# seismometer_lcdboard.net
KiCad netlist of a schematic drawn in EAGLE
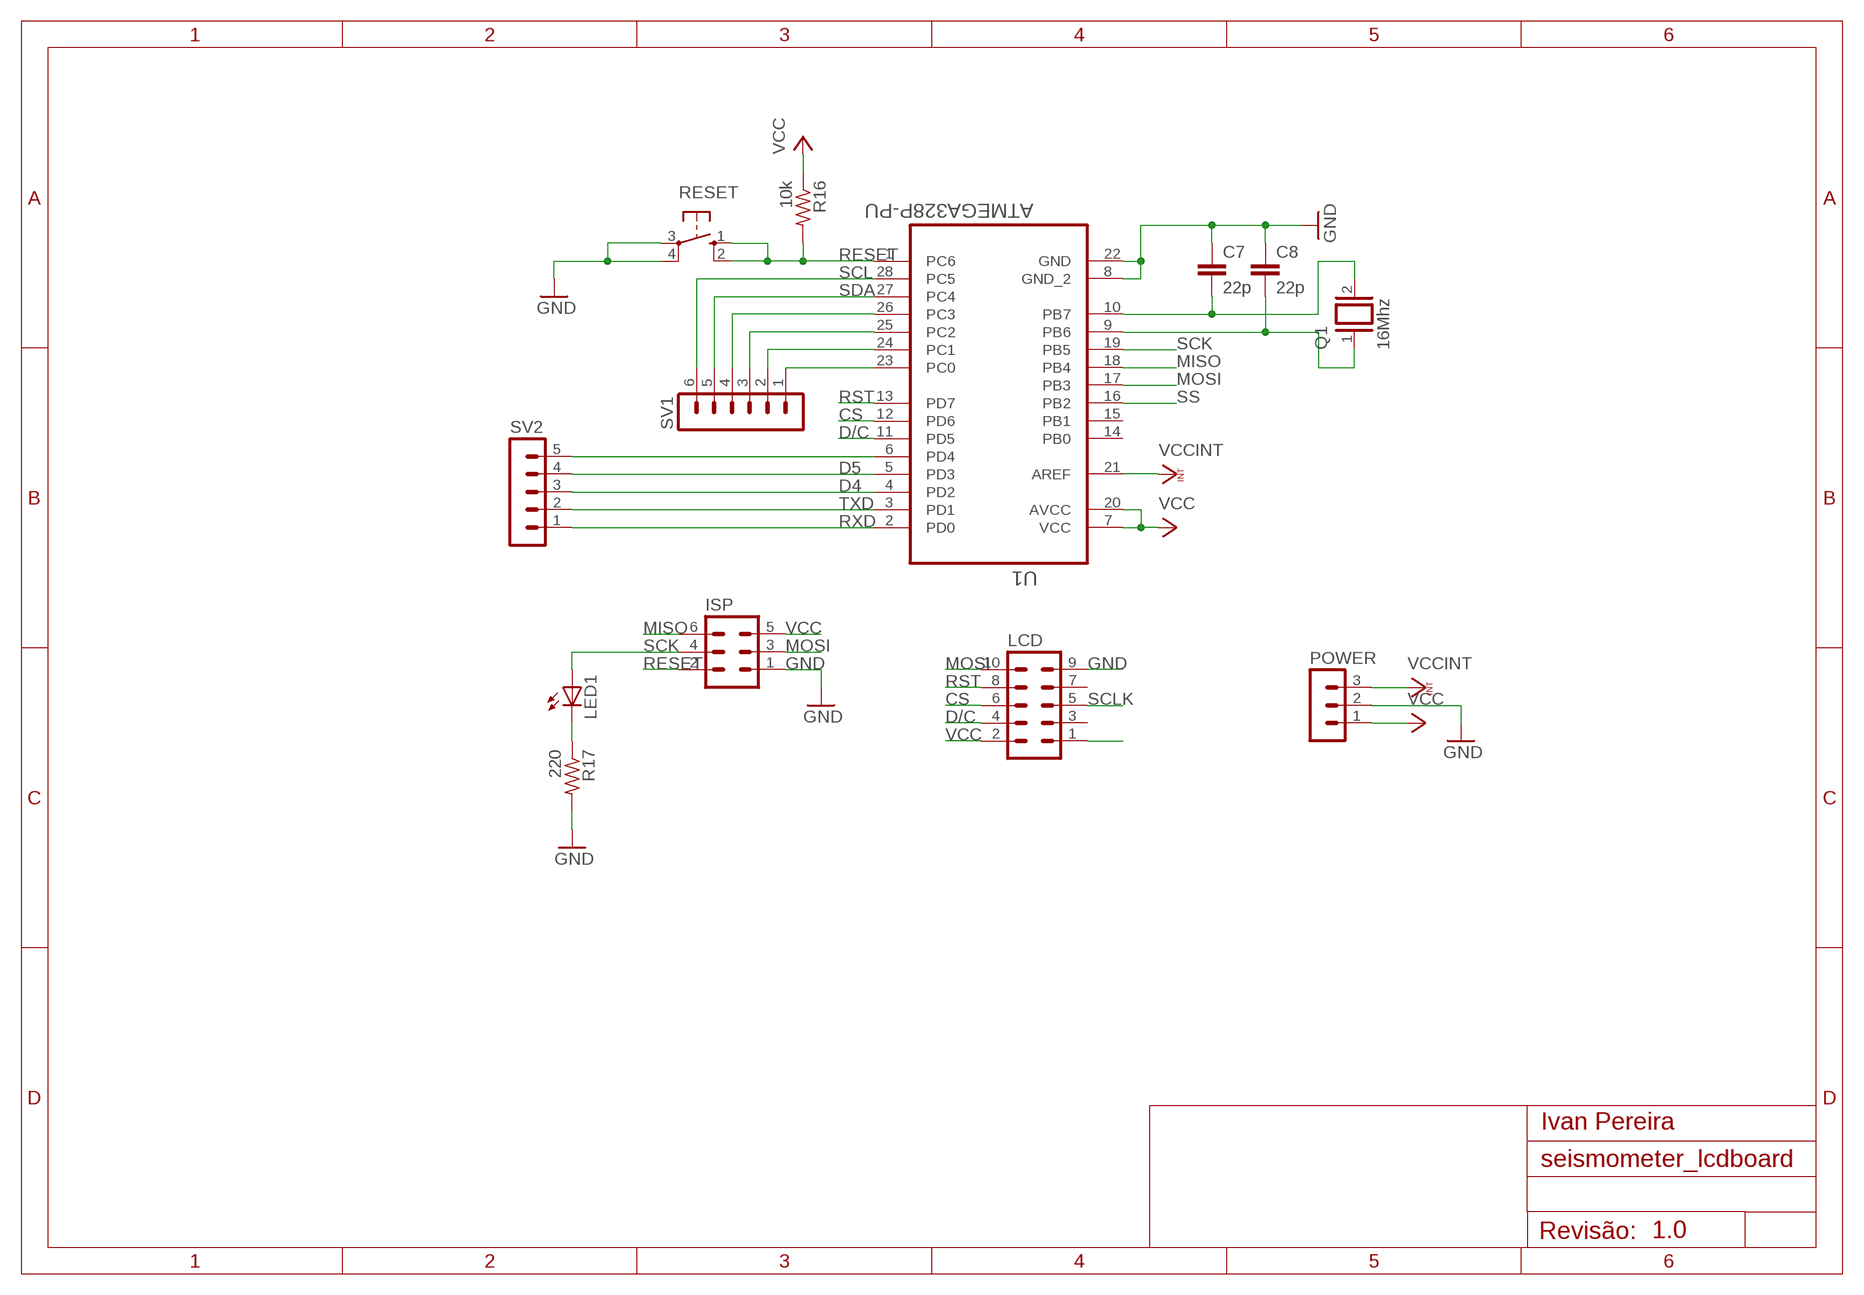
[diagram p0: schematic, sheet 1]

(export (version "E")
  (design (tool "Eeschema 10.0.6"))
  (components
    (comp (ref "C7")
      (value "22p")
      (footprint "eagle-import:C050-025X075")
      (libsource (lib "eagle-import") (part "C-EU050-025X075"))
    )
    (comp (ref "C8")
      (value "22p")
      (footprint "eagle-import:C050-025X075")
      (libsource (lib "eagle-import") (part "C-EU050-025X075"))
    )
    (comp (ref "ISP")
      (value "MA03-2")
      (footprint "eagle-import:MA03-2")
      (libsource (lib "eagle-import") (part "MA03-2"))
    )
    (comp (ref "LCD")
      (value "MA05-2")
      (footprint "eagle-import:MA05-2")
      (libsource (lib "eagle-import") (part "MA05-2"))
    )
    (comp (ref "LED1")
      (value "LED3MM")
      (footprint "eagle-import:LED3MM")
      (libsource (lib "eagle-import") (part "LED3MM"))
    )
    (comp (ref "POWER")
      (value "MA03-1")
      (footprint "eagle-import:MA03-1")
      (libsource (lib "eagle-import") (part "MA03-1"))
    )
    (comp (ref "Q1")
      (value "16Mhz")
      (footprint "eagle-import:QS")
      (libsource (lib "eagle-import") (part "XTAL/S"))
    )
    (comp (ref "R16")
      (value "10k")
      (footprint "eagle-import:0207_12")
      (libsource (lib "eagle-import") (part "R-US_0207/12"))
    )
    (comp (ref "R17")
      (value "220")
      (footprint "eagle-import:0207_12")
      (libsource (lib "eagle-import") (part "R-US_0207/12"))
    )
    (comp (ref "RESET")
      (value "10-XX")
      (footprint "eagle-import:B3F-10XX")
      (fields (field (name "MPN") "B3F-1000"))
      (libsource (lib "eagle-import") (part "10-XX"))
    )
    (comp (ref "SV1")
      (value "MA06-1")
      (footprint "eagle-import:MA06-1")
      (libsource (lib "eagle-import") (part "MA06-1"))
    )
    (comp (ref "SV2")
      (value "MA05-1")
      (footprint "eagle-import:MA05-1")
      (libsource (lib "eagle-import") (part "MA05-1"))
    )
    (comp (ref "U1")
      (value "ATMEGA328P-PU")
      (footprint "eagle-import:DIP254P762X457-28")
      (libsource (lib "eagle-import") (part "ATMEGA328P-PU"))
    )
  )
  (nets
    (net (code "1") (name "/CS") (class "Default")
      (node (ref "LCD") (pin "6") (pinfunction "6_6") (pintype "passive"))
      (node (ref "U1") (pin "12") (pinfunction "PD6_12") (pintype "bidirectional"))
    )
    (net (code "2") (name "/D4") (class "Default")
      (node (ref "SV2") (pin "3") (pinfunction "3_3") (pintype "passive"))
      (node (ref "U1") (pin "4") (pinfunction "PD2_4") (pintype "bidirectional"))
    )
    (net (code "3") (name "/D5") (class "Default")
      (node (ref "SV2") (pin "4") (pinfunction "4_4") (pintype "passive"))
      (node (ref "U1") (pin "5") (pinfunction "PD3_5") (pintype "bidirectional"))
    )
    (net (code "4") (name "/D{slash}C") (class "Default")
      (node (ref "LCD") (pin "4") (pinfunction "4_4") (pintype "passive"))
      (node (ref "U1") (pin "11") (pinfunction "PD5_11") (pintype "bidirectional"))
    )
    (net (code "5") (name "/MISO") (class "Default")
      (node (ref "ISP") (pin "6") (pinfunction "6_6") (pintype "passive"))
      (node (ref "U1") (pin "18") (pinfunction "PB4_18") (pintype "bidirectional"))
    )
    (net (code "6") (name "/MOSI") (class "Default")
      (node (ref "ISP") (pin "3") (pinfunction "3_3") (pintype "passive"))
      (node (ref "LCD") (pin "10") (pinfunction "10_10") (pintype "passive"))
      (node (ref "U1") (pin "17") (pinfunction "PB3_17") (pintype "bidirectional"))
    )
    (net (code "7") (name "/RESET") (class "Default")
      (node (ref "ISP") (pin "2") (pinfunction "2_2") (pintype "passive"))
      (node (ref "R16") (pin "2") (pinfunction "2_2") (pintype "passive"))
      (node (ref "RESET") (pin "1") (pinfunction "S_1") (pintype "passive"))
      (node (ref "RESET") (pin "2") (pinfunction "S1_2") (pintype "passive"))
      (node (ref "U1") (pin "1") (pinfunction "PC6_1") (pintype "bidirectional"))
    )
    (net (code "8") (name "/RST") (class "Default")
      (node (ref "LCD") (pin "8") (pinfunction "8_8") (pintype "passive"))
      (node (ref "U1") (pin "13") (pinfunction "PD7_13") (pintype "bidirectional"))
    )
    (net (code "9") (name "/RXD") (class "Default")
      (node (ref "SV2") (pin "1") (pinfunction "1_1") (pintype "passive"))
      (node (ref "U1") (pin "2") (pinfunction "PD0_2") (pintype "bidirectional"))
    )
    (net (code "10") (name "/SCK") (class "Default")
      (node (ref "ISP") (pin "4") (pinfunction "4_4") (pintype "passive"))
      (node (ref "LED1") (pin "A") (pinfunction "A_A") (pintype "passive"))
      (node (ref "U1") (pin "19") (pinfunction "PB5_19") (pintype "bidirectional"))
    )
    (net (code "11") (name "/SCL") (class "Default")
      (node (ref "SV1") (pin "6") (pinfunction "6_6") (pintype "passive"))
      (node (ref "U1") (pin "28") (pinfunction "PC5_28") (pintype "bidirectional"))
    )
    (net (code "12") (name "/SCLK") (class "Default")
      (node (ref "LCD") (pin "5") (pinfunction "5_5") (pintype "passive"))
    )
    (net (code "13") (name "/SDA") (class "Default")
      (node (ref "SV1") (pin "5") (pinfunction "5_5") (pintype "passive"))
      (node (ref "U1") (pin "27") (pinfunction "PC4_27") (pintype "bidirectional"))
    )
    (net (code "14") (name "/SS") (class "Default")
      (node (ref "U1") (pin "16") (pinfunction "PB2_16") (pintype "bidirectional"))
    )
    (net (code "15") (name "/TXD") (class "Default")
      (node (ref "SV2") (pin "2") (pinfunction "2_2") (pintype "passive"))
      (node (ref "U1") (pin "3") (pinfunction "PD1_3") (pintype "bidirectional"))
    )
    (net (code "16") (name "GND") (class "Default")
      (node (ref "C7") (pin "1") (pinfunction "1_1") (pintype "passive"))
      (node (ref "C8") (pin "1") (pinfunction "1_1") (pintype "passive"))
      (node (ref "ISP") (pin "1") (pinfunction "1_1") (pintype "passive"))
      (node (ref "LCD") (pin "9") (pinfunction "9_9") (pintype "passive"))
      (node (ref "POWER") (pin "2") (pinfunction "2_2") (pintype "passive"))
      (node (ref "R17") (pin "2") (pinfunction "2_2") (pintype "passive"))
      (node (ref "RESET") (pin "3") (pinfunction "P_3") (pintype "passive"))
      (node (ref "RESET") (pin "4") (pinfunction "P1_4") (pintype "passive"))
      (node (ref "U1") (pin "22") (pinfunction "GND_22") (pintype "passive"))
      (node (ref "U1") (pin "8") (pinfunction "GND_2_8") (pintype "passive"))
    )
    (net (code "17") (name "Net-(LED1-C)") (class "Default")
      (node (ref "LED1") (pin "K") (pinfunction "C_K") (pintype "passive"))
      (node (ref "R17") (pin "1") (pinfunction "1_1") (pintype "passive"))
    )
    (net (code "18") (name "Net-(U1-PB6)") (class "Default")
      (node (ref "C8") (pin "2") (pinfunction "2_2") (pintype "passive"))
      (node (ref "Q1") (pin "1") (pinfunction "1_1") (pintype "passive"))
      (node (ref "U1") (pin "9") (pinfunction "PB6_9") (pintype "bidirectional"))
    )
    (net (code "19") (name "Net-(U1-PB7)") (class "Default")
      (node (ref "C7") (pin "2") (pinfunction "2_2") (pintype "passive"))
      (node (ref "Q1") (pin "2") (pinfunction "2_2") (pintype "passive"))
      (node (ref "U1") (pin "10") (pinfunction "PB7_10") (pintype "bidirectional"))
    )
    (net (code "20") (name "Net-(U1-PC0)") (class "Default")
      (node (ref "SV1") (pin "1") (pinfunction "1_1") (pintype "passive"))
      (node (ref "U1") (pin "23") (pinfunction "PC0_23") (pintype "bidirectional"))
    )
    (net (code "21") (name "Net-(U1-PC1)") (class "Default")
      (node (ref "SV1") (pin "2") (pinfunction "2_2") (pintype "passive"))
      (node (ref "U1") (pin "24") (pinfunction "PC1_24") (pintype "bidirectional"))
    )
    (net (code "22") (name "Net-(U1-PC2)") (class "Default")
      (node (ref "SV1") (pin "3") (pinfunction "3_3") (pintype "passive"))
      (node (ref "U1") (pin "25") (pinfunction "PC2_25") (pintype "bidirectional"))
    )
    (net (code "23") (name "Net-(U1-PC3)") (class "Default")
      (node (ref "SV1") (pin "4") (pinfunction "4_4") (pintype "passive"))
      (node (ref "U1") (pin "26") (pinfunction "PC3_26") (pintype "bidirectional"))
    )
    (net (code "24") (name "Net-(U1-PD4)") (class "Default")
      (node (ref "SV2") (pin "5") (pinfunction "5_5") (pintype "passive"))
      (node (ref "U1") (pin "6") (pinfunction "PD4_6") (pintype "bidirectional"))
    )
    (net (code "25") (name "VCC") (class "Default")
      (node (ref "ISP") (pin "5") (pinfunction "5_5") (pintype "passive"))
      (node (ref "LCD") (pin "2") (pinfunction "2_2") (pintype "passive"))
      (node (ref "POWER") (pin "1") (pinfunction "1_1") (pintype "passive"))
      (node (ref "R16") (pin "1") (pinfunction "1_1") (pintype "passive"))
      (node (ref "U1") (pin "20") (pinfunction "AVCC_20") (pintype "power_in"))
      (node (ref "U1") (pin "7") (pinfunction "VCC_7") (pintype "power_in"))
    )
    (net (code "26") (name "VCCINT") (class "Default")
      (node (ref "POWER") (pin "3") (pinfunction "3_3") (pintype "passive"))
      (node (ref "U1") (pin "21") (pinfunction "AREF_21") (pintype "input"))
    )
    (net (code "27") (name "unconnected-(LCD-Pad1)") (class "Default")
      (node (ref "LCD") (pin "1") (pinfunction "1_1") (pintype "passive"))
    )
    (net (code "28") (name "unconnected-(LCD-Pad3)") (class "Default")
      (node (ref "LCD") (pin "3") (pinfunction "3_3") (pintype "passive"))
    )
    (net (code "29") (name "unconnected-(LCD-Pad7)") (class "Default")
      (node (ref "LCD") (pin "7") (pinfunction "7_7") (pintype "passive"))
    )
    (net (code "30") (name "unconnected-(U1-PB0-Pad14)") (class "Default")
      (node (ref "U1") (pin "14") (pinfunction "PB0_14") (pintype "bidirectional"))
    )
    (net (code "31") (name "unconnected-(U1-PB1-Pad15)") (class "Default")
      (node (ref "U1") (pin "15") (pinfunction "PB1_15") (pintype "bidirectional"))
    )
  )
)
